# Top.net
KiCad netlist of a schematic drawn in Altium Designer
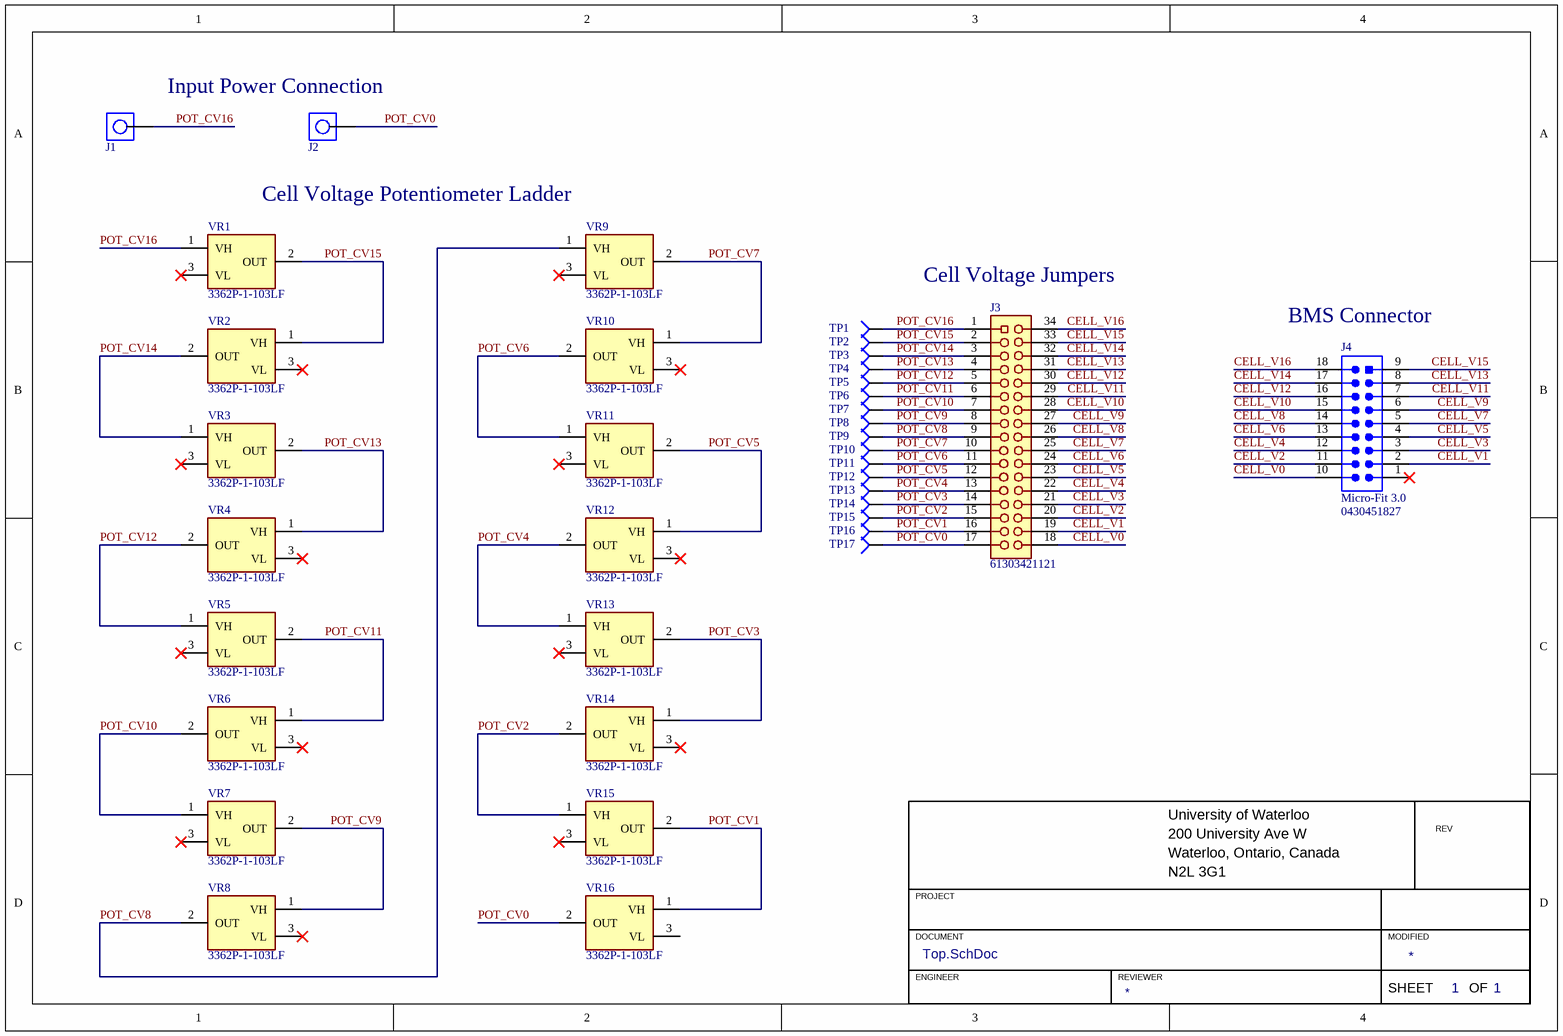
[diagram p0: Top.SchDoc]

(export (version "E")
  (design (tool "Eeschema 10.0.6"))
  (components
    (comp (ref "J1")
      (value "105-1102-001")
      (footprint "CINCH_BANANA_JACK_RED")
      (description "CONN TIP JACK SOLDER RED")
      (libsource (lib "Personal_Schematic_Library_2022") (part "CON_BANANA_RED_5A"))
    )
    (comp (ref "J2")
      (value "105-1103-001")
      (footprint "CINCH_BANANA_JACK_RED")
      (description "CONN TIP JACK SOLDER BLACK")
      (libsource (lib "Personal_Schematic_Library_2022") (part "CON_BANANA_BLACK_5A"))
    )
    (comp (ref "J3")
      (value "HEADER 17X2")
      (footprint "HEADER_2x17")
      (description "CONN HEADER VERT 34POS 2.54MM")
      (fields (field (name "MANUFACTURER PART NUMBER 1") "61303421121"))
      (libsource (lib "Personal_Schematic_Library_2022") (part "HEADER 17X2"))
    )
    (comp (ref "J4")
      (value "0430451827")
      (footprint "MOLEX-0430451827")
      (description "CONN HEADER VERT 18POS 3MM")
      (fields
        (field (name "FAMILY") "Micro-Fit 3.0")
        (field (name "MANUFACTURER PART NUMBER 1") "0430451827")
      )
      (libsource (lib "Personal_Schematic_Library_2022") (part "CON_MOLEX-HDR_9x2_TH"))
    )
    (comp (ref "TP1")
      (value "TESTPOINT_1MM_SQUARE")
      (footprint "TESTPOINT_SQUARE_1MM")
      (description "TESTPOINT 1MM SQUARE")
      (libsource (lib "Personal_Schematic_Library_2022") (part "TESTPOINT_1MM_SQUARE"))
    )
    (comp (ref "TP2")
      (value "TESTPOINT_1MM_SQUARE")
      (footprint "TESTPOINT_SQUARE_1MM")
      (description "TESTPOINT 1MM SQUARE")
      (libsource (lib "Personal_Schematic_Library_2022") (part "TESTPOINT_1MM_SQUARE"))
    )
    (comp (ref "TP3")
      (value "TESTPOINT_1MM_SQUARE")
      (footprint "TESTPOINT_SQUARE_1MM")
      (description "TESTPOINT 1MM SQUARE")
      (libsource (lib "Personal_Schematic_Library_2022") (part "TESTPOINT_1MM_SQUARE"))
    )
    (comp (ref "TP4")
      (value "TESTPOINT_1MM_SQUARE")
      (footprint "TESTPOINT_SQUARE_1MM")
      (description "TESTPOINT 1MM SQUARE")
      (libsource (lib "Personal_Schematic_Library_2022") (part "TESTPOINT_1MM_SQUARE"))
    )
    (comp (ref "TP5")
      (value "TESTPOINT_1MM_SQUARE")
      (footprint "TESTPOINT_SQUARE_1MM")
      (description "TESTPOINT 1MM SQUARE")
      (libsource (lib "Personal_Schematic_Library_2022") (part "TESTPOINT_1MM_SQUARE"))
    )
    (comp (ref "TP6")
      (value "TESTPOINT_1MM_SQUARE")
      (footprint "TESTPOINT_SQUARE_1MM")
      (description "TESTPOINT 1MM SQUARE")
      (libsource (lib "Personal_Schematic_Library_2022") (part "TESTPOINT_1MM_SQUARE"))
    )
    (comp (ref "TP7")
      (value "TESTPOINT_1MM_SQUARE")
      (footprint "TESTPOINT_SQUARE_1MM")
      (description "TESTPOINT 1MM SQUARE")
      (libsource (lib "Personal_Schematic_Library_2022") (part "TESTPOINT_1MM_SQUARE"))
    )
    (comp (ref "TP8")
      (value "TESTPOINT_1MM_SQUARE")
      (footprint "TESTPOINT_SQUARE_1MM")
      (description "TESTPOINT 1MM SQUARE")
      (libsource (lib "Personal_Schematic_Library_2022") (part "TESTPOINT_1MM_SQUARE"))
    )
    (comp (ref "TP9")
      (value "TESTPOINT_1MM_SQUARE")
      (footprint "TESTPOINT_SQUARE_1MM")
      (description "TESTPOINT 1MM SQUARE")
      (libsource (lib "Personal_Schematic_Library_2022") (part "TESTPOINT_1MM_SQUARE"))
    )
    (comp (ref "TP10")
      (value "TESTPOINT_1MM_SQUARE")
      (footprint "TESTPOINT_SQUARE_1MM")
      (description "TESTPOINT 1MM SQUARE")
      (libsource (lib "Personal_Schematic_Library_2022") (part "TESTPOINT_1MM_SQUARE"))
    )
    (comp (ref "TP11")
      (value "TESTPOINT_1MM_SQUARE")
      (footprint "TESTPOINT_SQUARE_1MM")
      (description "TESTPOINT 1MM SQUARE")
      (libsource (lib "Personal_Schematic_Library_2022") (part "TESTPOINT_1MM_SQUARE"))
    )
    (comp (ref "TP12")
      (value "TESTPOINT_1MM_SQUARE")
      (footprint "TESTPOINT_SQUARE_1MM")
      (description "TESTPOINT 1MM SQUARE")
      (libsource (lib "Personal_Schematic_Library_2022") (part "TESTPOINT_1MM_SQUARE"))
    )
    (comp (ref "TP13")
      (value "TESTPOINT_1MM_SQUARE")
      (footprint "TESTPOINT_SQUARE_1MM")
      (description "TESTPOINT 1MM SQUARE")
      (libsource (lib "Personal_Schematic_Library_2022") (part "TESTPOINT_1MM_SQUARE"))
    )
    (comp (ref "TP14")
      (value "TESTPOINT_1MM_SQUARE")
      (footprint "TESTPOINT_SQUARE_1MM")
      (description "TESTPOINT 1MM SQUARE")
      (libsource (lib "Personal_Schematic_Library_2022") (part "TESTPOINT_1MM_SQUARE"))
    )
    (comp (ref "TP15")
      (value "TESTPOINT_1MM_SQUARE")
      (footprint "TESTPOINT_SQUARE_1MM")
      (description "TESTPOINT 1MM SQUARE")
      (libsource (lib "Personal_Schematic_Library_2022") (part "TESTPOINT_1MM_SQUARE"))
    )
    (comp (ref "TP16")
      (value "TESTPOINT_1MM_SQUARE")
      (footprint "TESTPOINT_SQUARE_1MM")
      (description "TESTPOINT 1MM SQUARE")
      (libsource (lib "Personal_Schematic_Library_2022") (part "TESTPOINT_1MM_SQUARE"))
    )
    (comp (ref "TP17")
      (value "TESTPOINT_1MM_SQUARE")
      (footprint "TESTPOINT_SQUARE_1MM")
      (description "TESTPOINT 1MM SQUARE")
      (libsource (lib "Personal_Schematic_Library_2022") (part "TESTPOINT_1MM_SQUARE"))
    )
    (comp (ref "VR1")
      (value "POT_10K_TRIM")
      (footprint "TRIMPOT_3362")
      (description "TRIMMER 10K OHM 0.5W PC PIN TOP")
      (fields (field (name "MANUFACTURER PART NUMBER 1") "3362P-1-103LF"))
      (libsource (lib "Personal_Schematic_Library_2022") (part "POT_10K_TRIM"))
    )
    (comp (ref "VR2")
      (value "POT_10K_TRIM")
      (footprint "TRIMPOT_3362")
      (description "TRIMMER 10K OHM 0.5W PC PIN TOP")
      (fields (field (name "MANUFACTURER PART NUMBER 1") "3362P-1-103LF"))
      (libsource (lib "") (part "POT_10K_TRIM_1"))
    )
    (comp (ref "VR3")
      (value "POT_10K_TRIM")
      (footprint "TRIMPOT_3362")
      (description "TRIMMER 10K OHM 0.5W PC PIN TOP")
      (fields (field (name "MANUFACTURER PART NUMBER 1") "3362P-1-103LF"))
      (libsource (lib "Personal_Schematic_Library_2022") (part "POT_10K_TRIM"))
    )
    (comp (ref "VR4")
      (value "POT_10K_TRIM")
      (footprint "TRIMPOT_3362")
      (description "TRIMMER 10K OHM 0.5W PC PIN TOP")
      (fields (field (name "MANUFACTURER PART NUMBER 1") "3362P-1-103LF"))
      (libsource (lib "") (part "POT_10K_TRIM_1"))
    )
    (comp (ref "VR5")
      (value "POT_10K_TRIM")
      (footprint "TRIMPOT_3362")
      (description "TRIMMER 10K OHM 0.5W PC PIN TOP")
      (fields (field (name "MANUFACTURER PART NUMBER 1") "3362P-1-103LF"))
      (libsource (lib "Personal_Schematic_Library_2022") (part "POT_10K_TRIM"))
    )
    (comp (ref "VR6")
      (value "POT_10K_TRIM")
      (footprint "TRIMPOT_3362")
      (description "TRIMMER 10K OHM 0.5W PC PIN TOP")
      (fields (field (name "MANUFACTURER PART NUMBER 1") "3362P-1-103LF"))
      (libsource (lib "") (part "POT_10K_TRIM_1"))
    )
    (comp (ref "VR7")
      (value "POT_10K_TRIM")
      (footprint "TRIMPOT_3362")
      (description "TRIMMER 10K OHM 0.5W PC PIN TOP")
      (fields (field (name "MANUFACTURER PART NUMBER 1") "3362P-1-103LF"))
      (libsource (lib "Personal_Schematic_Library_2022") (part "POT_10K_TRIM"))
    )
    (comp (ref "VR8")
      (value "POT_10K_TRIM")
      (footprint "TRIMPOT_3362")
      (description "TRIMMER 10K OHM 0.5W PC PIN TOP")
      (fields (field (name "MANUFACTURER PART NUMBER 1") "3362P-1-103LF"))
      (libsource (lib "") (part "POT_10K_TRIM_1"))
    )
    (comp (ref "VR9")
      (value "POT_10K_TRIM")
      (footprint "TRIMPOT_3362")
      (description "TRIMMER 10K OHM 0.5W PC PIN TOP")
      (fields (field (name "MANUFACTURER PART NUMBER 1") "3362P-1-103LF"))
      (libsource (lib "Personal_Schematic_Library_2022") (part "POT_10K_TRIM"))
    )
    (comp (ref "VR10")
      (value "POT_10K_TRIM")
      (footprint "TRIMPOT_3362")
      (description "TRIMMER 10K OHM 0.5W PC PIN TOP")
      (fields (field (name "MANUFACTURER PART NUMBER 1") "3362P-1-103LF"))
      (libsource (lib "") (part "POT_10K_TRIM_1"))
    )
    (comp (ref "VR11")
      (value "POT_10K_TRIM")
      (footprint "TRIMPOT_3362")
      (description "TRIMMER 10K OHM 0.5W PC PIN TOP")
      (fields (field (name "MANUFACTURER PART NUMBER 1") "3362P-1-103LF"))
      (libsource (lib "Personal_Schematic_Library_2022") (part "POT_10K_TRIM"))
    )
    (comp (ref "VR12")
      (value "POT_10K_TRIM")
      (footprint "TRIMPOT_3362")
      (description "TRIMMER 10K OHM 0.5W PC PIN TOP")
      (fields (field (name "MANUFACTURER PART NUMBER 1") "3362P-1-103LF"))
      (libsource (lib "") (part "POT_10K_TRIM_1"))
    )
    (comp (ref "VR13")
      (value "POT_10K_TRIM")
      (footprint "TRIMPOT_3362")
      (description "TRIMMER 10K OHM 0.5W PC PIN TOP")
      (fields (field (name "MANUFACTURER PART NUMBER 1") "3362P-1-103LF"))
      (libsource (lib "Personal_Schematic_Library_2022") (part "POT_10K_TRIM"))
    )
    (comp (ref "VR14")
      (value "POT_10K_TRIM")
      (footprint "TRIMPOT_3362")
      (description "TRIMMER 10K OHM 0.5W PC PIN TOP")
      (fields (field (name "MANUFACTURER PART NUMBER 1") "3362P-1-103LF"))
      (libsource (lib "") (part "POT_10K_TRIM_1"))
    )
    (comp (ref "VR15")
      (value "POT_10K_TRIM")
      (footprint "TRIMPOT_3362")
      (description "TRIMMER 10K OHM 0.5W PC PIN TOP")
      (fields (field (name "MANUFACTURER PART NUMBER 1") "3362P-1-103LF"))
      (libsource (lib "Personal_Schematic_Library_2022") (part "POT_10K_TRIM"))
    )
    (comp (ref "VR16")
      (value "POT_10K_TRIM")
      (footprint "TRIMPOT_3362")
      (description "TRIMMER 10K OHM 0.5W PC PIN TOP")
      (fields (field (name "MANUFACTURER PART NUMBER 1") "3362P-1-103LF"))
      (libsource (lib "") (part "POT_10K_TRIM_1"))
    )
  )
  (nets
    (net (code "1") (name "/CELL_V0") (class "Default")
      (node (ref "J3") (pin "18") (pinfunction "18_18") (pintype "passive"))
      (node (ref "J4") (pin "10") (pinfunction "10_10") (pintype "passive"))
    )
    (net (code "2") (name "/CELL_V1") (class "Default")
      (node (ref "J3") (pin "19") (pinfunction "19_19") (pintype "passive"))
      (node (ref "J4") (pin "2") (pinfunction "2_2") (pintype "passive"))
    )
    (net (code "3") (name "/CELL_V2") (class "Default")
      (node (ref "J3") (pin "20") (pinfunction "20_20") (pintype "passive"))
      (node (ref "J4") (pin "11") (pinfunction "11_11") (pintype "passive"))
    )
    (net (code "4") (name "/CELL_V3") (class "Default")
      (node (ref "J3") (pin "21") (pinfunction "21_21") (pintype "passive"))
      (node (ref "J4") (pin "3") (pinfunction "3_3") (pintype "passive"))
    )
    (net (code "5") (name "/CELL_V4") (class "Default")
      (node (ref "J3") (pin "22") (pinfunction "22_22") (pintype "passive"))
      (node (ref "J4") (pin "12") (pinfunction "12_12") (pintype "passive"))
    )
    (net (code "6") (name "/CELL_V5") (class "Default")
      (node (ref "J3") (pin "23") (pinfunction "23_23") (pintype "passive"))
      (node (ref "J4") (pin "4") (pinfunction "4_4") (pintype "passive"))
    )
    (net (code "7") (name "/CELL_V6") (class "Default")
      (node (ref "J3") (pin "24") (pinfunction "24_24") (pintype "passive"))
      (node (ref "J4") (pin "13") (pinfunction "13_13") (pintype "passive"))
    )
    (net (code "8") (name "/CELL_V7") (class "Default")
      (node (ref "J3") (pin "25") (pinfunction "25_25") (pintype "passive"))
      (node (ref "J4") (pin "5") (pinfunction "5_5") (pintype "passive"))
    )
    (net (code "9") (name "/CELL_V8") (class "Default")
      (node (ref "J3") (pin "26") (pinfunction "26_26") (pintype "passive"))
      (node (ref "J4") (pin "14") (pinfunction "14_14") (pintype "passive"))
    )
    (net (code "10") (name "/CELL_V9") (class "Default")
      (node (ref "J3") (pin "27") (pinfunction "27_27") (pintype "passive"))
      (node (ref "J4") (pin "6") (pinfunction "6_6") (pintype "passive"))
    )
    (net (code "11") (name "/CELL_V10") (class "Default")
      (node (ref "J3") (pin "28") (pinfunction "28_28") (pintype "passive"))
      (node (ref "J4") (pin "15") (pinfunction "15_15") (pintype "passive"))
    )
    (net (code "12") (name "/CELL_V11") (class "Default")
      (node (ref "J3") (pin "29") (pinfunction "29_29") (pintype "passive"))
      (node (ref "J4") (pin "7") (pinfunction "7_7") (pintype "passive"))
    )
    (net (code "13") (name "/CELL_V12") (class "Default")
      (node (ref "J3") (pin "30") (pinfunction "30_30") (pintype "passive"))
      (node (ref "J4") (pin "16") (pinfunction "16_16") (pintype "passive"))
    )
    (net (code "14") (name "/CELL_V13") (class "Default")
      (node (ref "J3") (pin "31") (pinfunction "31_31") (pintype "passive"))
      (node (ref "J4") (pin "8") (pinfunction "8_8") (pintype "passive"))
    )
    (net (code "15") (name "/CELL_V14") (class "Default")
      (node (ref "J3") (pin "32") (pinfunction "32_32") (pintype "passive"))
      (node (ref "J4") (pin "17") (pinfunction "17_17") (pintype "passive"))
    )
    (net (code "16") (name "/CELL_V15") (class "Default")
      (node (ref "J3") (pin "33") (pinfunction "33_33") (pintype "passive"))
      (node (ref "J4") (pin "9") (pinfunction "9_9") (pintype "passive"))
    )
    (net (code "17") (name "/CELL_V16") (class "Default")
      (node (ref "J3") (pin "34") (pinfunction "34_34") (pintype "passive"))
      (node (ref "J4") (pin "18") (pinfunction "18_18") (pintype "passive"))
    )
    (net (code "18") (name "/POT_CV0") (class "Default")
      (node (ref "J2") (pin "1") (pinfunction "1_1") (pintype "power_in"))
      (node (ref "J3") (pin "17") (pinfunction "17_17") (pintype "passive"))
      (node (ref "TP17") (pin "1") (pinfunction "=value_1") (pintype "passive"))
      (node (ref "VR16") (pin "2") (pinfunction "OUT_2") (pintype "passive"))
    )
    (net (code "19") (name "/POT_CV1") (class "Default")
      (node (ref "J3") (pin "16") (pinfunction "16_16") (pintype "passive"))
      (node (ref "TP16") (pin "1") (pinfunction "=value_1") (pintype "passive"))
      (node (ref "VR15") (pin "2") (pinfunction "OUT_2") (pintype "passive"))
      (node (ref "VR16") (pin "1") (pinfunction "VH_1") (pintype "passive"))
    )
    (net (code "20") (name "/POT_CV2") (class "Default")
      (node (ref "J3") (pin "15") (pinfunction "15_15") (pintype "passive"))
      (node (ref "TP15") (pin "1") (pinfunction "=value_1") (pintype "passive"))
      (node (ref "VR14") (pin "2") (pinfunction "OUT_2") (pintype "passive"))
      (node (ref "VR15") (pin "1") (pinfunction "VH_1") (pintype "passive"))
    )
    (net (code "21") (name "/POT_CV3") (class "Default")
      (node (ref "J3") (pin "14") (pinfunction "14_14") (pintype "passive"))
      (node (ref "TP14") (pin "1") (pinfunction "=value_1") (pintype "passive"))
      (node (ref "VR13") (pin "2") (pinfunction "OUT_2") (pintype "passive"))
      (node (ref "VR14") (pin "1") (pinfunction "VH_1") (pintype "passive"))
    )
    (net (code "22") (name "/POT_CV4") (class "Default")
      (node (ref "J3") (pin "13") (pinfunction "13_13") (pintype "passive"))
      (node (ref "TP13") (pin "1") (pinfunction "=value_1") (pintype "passive"))
      (node (ref "VR12") (pin "2") (pinfunction "OUT_2") (pintype "passive"))
      (node (ref "VR13") (pin "1") (pinfunction "VH_1") (pintype "passive"))
    )
    (net (code "23") (name "/POT_CV5") (class "Default")
      (node (ref "J3") (pin "12") (pinfunction "12_12") (pintype "passive"))
      (node (ref "TP12") (pin "1") (pinfunction "=value_1") (pintype "passive"))
      (node (ref "VR11") (pin "2") (pinfunction "OUT_2") (pintype "passive"))
      (node (ref "VR12") (pin "1") (pinfunction "VH_1") (pintype "passive"))
    )
    (net (code "24") (name "/POT_CV6") (class "Default")
      (node (ref "J3") (pin "11") (pinfunction "11_11") (pintype "passive"))
      (node (ref "TP11") (pin "1") (pinfunction "=value_1") (pintype "passive"))
      (node (ref "VR10") (pin "2") (pinfunction "OUT_2") (pintype "passive"))
      (node (ref "VR11") (pin "1") (pinfunction "VH_1") (pintype "passive"))
    )
    (net (code "25") (name "/POT_CV7") (class "Default")
      (node (ref "J3") (pin "10") (pinfunction "10_10") (pintype "passive"))
      (node (ref "TP10") (pin "1") (pinfunction "=value_1") (pintype "passive"))
      (node (ref "VR10") (pin "1") (pinfunction "VH_1") (pintype "passive"))
      (node (ref "VR9") (pin "2") (pinfunction "OUT_2") (pintype "passive"))
    )
    (net (code "26") (name "/POT_CV8") (class "Default")
      (node (ref "J3") (pin "9") (pinfunction "9_9") (pintype "passive"))
      (node (ref "TP9") (pin "1") (pinfunction "=value_1") (pintype "passive"))
      (node (ref "VR8") (pin "2") (pinfunction "OUT_2") (pintype "passive"))
      (node (ref "VR9") (pin "1") (pinfunction "VH_1") (pintype "passive"))
    )
    (net (code "27") (name "/POT_CV9") (class "Default")
      (node (ref "J3") (pin "8") (pinfunction "8_8") (pintype "passive"))
      (node (ref "TP8") (pin "1") (pinfunction "=value_1") (pintype "passive"))
      (node (ref "VR7") (pin "2") (pinfunction "OUT_2") (pintype "passive"))
      (node (ref "VR8") (pin "1") (pinfunction "VH_1") (pintype "passive"))
    )
    (net (code "28") (name "/POT_CV10") (class "Default")
      (node (ref "J3") (pin "7") (pinfunction "7_7") (pintype "passive"))
      (node (ref "TP7") (pin "1") (pinfunction "=value_1") (pintype "passive"))
      (node (ref "VR6") (pin "2") (pinfunction "OUT_2") (pintype "passive"))
      (node (ref "VR7") (pin "1") (pinfunction "VH_1") (pintype "passive"))
    )
    (net (code "29") (name "/POT_CV11") (class "Default")
      (node (ref "J3") (pin "6") (pinfunction "6_6") (pintype "passive"))
      (node (ref "TP6") (pin "1") (pinfunction "=value_1") (pintype "passive"))
      (node (ref "VR5") (pin "2") (pinfunction "OUT_2") (pintype "passive"))
      (node (ref "VR6") (pin "1") (pinfunction "VH_1") (pintype "passive"))
    )
    (net (code "30") (name "/POT_CV12") (class "Default")
      (node (ref "J3") (pin "5") (pinfunction "5_5") (pintype "passive"))
      (node (ref "TP5") (pin "1") (pinfunction "=value_1") (pintype "passive"))
      (node (ref "VR4") (pin "2") (pinfunction "OUT_2") (pintype "passive"))
      (node (ref "VR5") (pin "1") (pinfunction "VH_1") (pintype "passive"))
    )
    (net (code "31") (name "/POT_CV13") (class "Default")
      (node (ref "J3") (pin "4") (pinfunction "4_4") (pintype "passive"))
      (node (ref "TP4") (pin "1") (pinfunction "=value_1") (pintype "passive"))
      (node (ref "VR3") (pin "2") (pinfunction "OUT_2") (pintype "passive"))
      (node (ref "VR4") (pin "1") (pinfunction "VH_1") (pintype "passive"))
    )
    (net (code "32") (name "/POT_CV14") (class "Default")
      (node (ref "J3") (pin "3") (pinfunction "3_3") (pintype "passive"))
      (node (ref "TP3") (pin "1") (pinfunction "=value_1") (pintype "passive"))
      (node (ref "VR2") (pin "2") (pinfunction "OUT_2") (pintype "passive"))
      (node (ref "VR3") (pin "1") (pinfunction "VH_1") (pintype "passive"))
    )
    (net (code "33") (name "/POT_CV15") (class "Default")
      (node (ref "J3") (pin "2") (pinfunction "2_2") (pintype "passive"))
      (node (ref "TP2") (pin "1") (pinfunction "=value_1") (pintype "passive"))
      (node (ref "VR1") (pin "2") (pinfunction "OUT_2") (pintype "passive"))
      (node (ref "VR2") (pin "1") (pinfunction "VH_1") (pintype "passive"))
    )
    (net (code "34") (name "/POT_CV16") (class "Default")
      (node (ref "J1") (pin "1") (pinfunction "1_1") (pintype "power_in"))
      (node (ref "J3") (pin "1") (pinfunction "VCC_1") (pintype "passive"))
      (node (ref "TP1") (pin "1") (pinfunction "=value_1") (pintype "passive"))
      (node (ref "VR1") (pin "1") (pinfunction "VH_1") (pintype "passive"))
    )
    (net (code "35") (name "unconnected-(J4-Pad1)") (class "Default")
      (node (ref "J4") (pin "1") (pinfunction "1_1") (pintype "passive+no_connect"))
    )
    (net (code "36") (name "unconnected-(VR1-VL-Pad3)") (class "Default")
      (node (ref "VR1") (pin "3") (pinfunction "VL_3") (pintype "passive+no_connect"))
    )
    (net (code "37") (name "unconnected-(VR2-VL-Pad3)") (class "Default")
      (node (ref "VR2") (pin "3") (pinfunction "VL_3") (pintype "passive+no_connect"))
    )
    (net (code "38") (name "unconnected-(VR3-VL-Pad3)") (class "Default")
      (node (ref "VR3") (pin "3") (pinfunction "VL_3") (pintype "passive+no_connect"))
    )
    (net (code "39") (name "unconnected-(VR4-VL-Pad3)") (class "Default")
      (node (ref "VR4") (pin "3") (pinfunction "VL_3") (pintype "passive+no_connect"))
    )
    (net (code "40") (name "unconnected-(VR5-VL-Pad3)") (class "Default")
      (node (ref "VR5") (pin "3") (pinfunction "VL_3") (pintype "passive+no_connect"))
    )
    (net (code "41") (name "unconnected-(VR6-VL-Pad3)") (class "Default")
      (node (ref "VR6") (pin "3") (pinfunction "VL_3") (pintype "passive+no_connect"))
    )
    (net (code "42") (name "unconnected-(VR7-VL-Pad3)") (class "Default")
      (node (ref "VR7") (pin "3") (pinfunction "VL_3") (pintype "passive+no_connect"))
    )
    (net (code "43") (name "unconnected-(VR8-VL-Pad3)") (class "Default")
      (node (ref "VR8") (pin "3") (pinfunction "VL_3") (pintype "passive+no_connect"))
    )
    (net (code "44") (name "unconnected-(VR9-VL-Pad3)") (class "Default")
      (node (ref "VR9") (pin "3") (pinfunction "VL_3") (pintype "passive+no_connect"))
    )
    (net (code "45") (name "unconnected-(VR10-VL-Pad3)") (class "Default")
      (node (ref "VR10") (pin "3") (pinfunction "VL_3") (pintype "passive+no_connect"))
    )
    (net (code "46") (name "unconnected-(VR11-VL-Pad3)") (class "Default")
      (node (ref "VR11") (pin "3") (pinfunction "VL_3") (pintype "passive+no_connect"))
    )
    (net (code "47") (name "unconnected-(VR12-VL-Pad3)") (class "Default")
      (node (ref "VR12") (pin "3") (pinfunction "VL_3") (pintype "passive+no_connect"))
    )
    (net (code "48") (name "unconnected-(VR13-VL-Pad3)") (class "Default")
      (node (ref "VR13") (pin "3") (pinfunction "VL_3") (pintype "passive+no_connect"))
    )
    (net (code "49") (name "unconnected-(VR14-VL-Pad3)") (class "Default")
      (node (ref "VR14") (pin "3") (pinfunction "VL_3") (pintype "passive+no_connect"))
    )
    (net (code "50") (name "unconnected-(VR15-VL-Pad3)") (class "Default")
      (node (ref "VR15") (pin "3") (pinfunction "VL_3") (pintype "passive+no_connect"))
    )
    (net (code "51") (name "unconnected-(VR16-VL-Pad3)") (class "Default")
      (node (ref "VR16") (pin "3") (pinfunction "VL_3") (pintype "passive"))
    )
  )
)
